# Stockwaage.net
KiCad netlist of a schematic drawn in EasyEDA
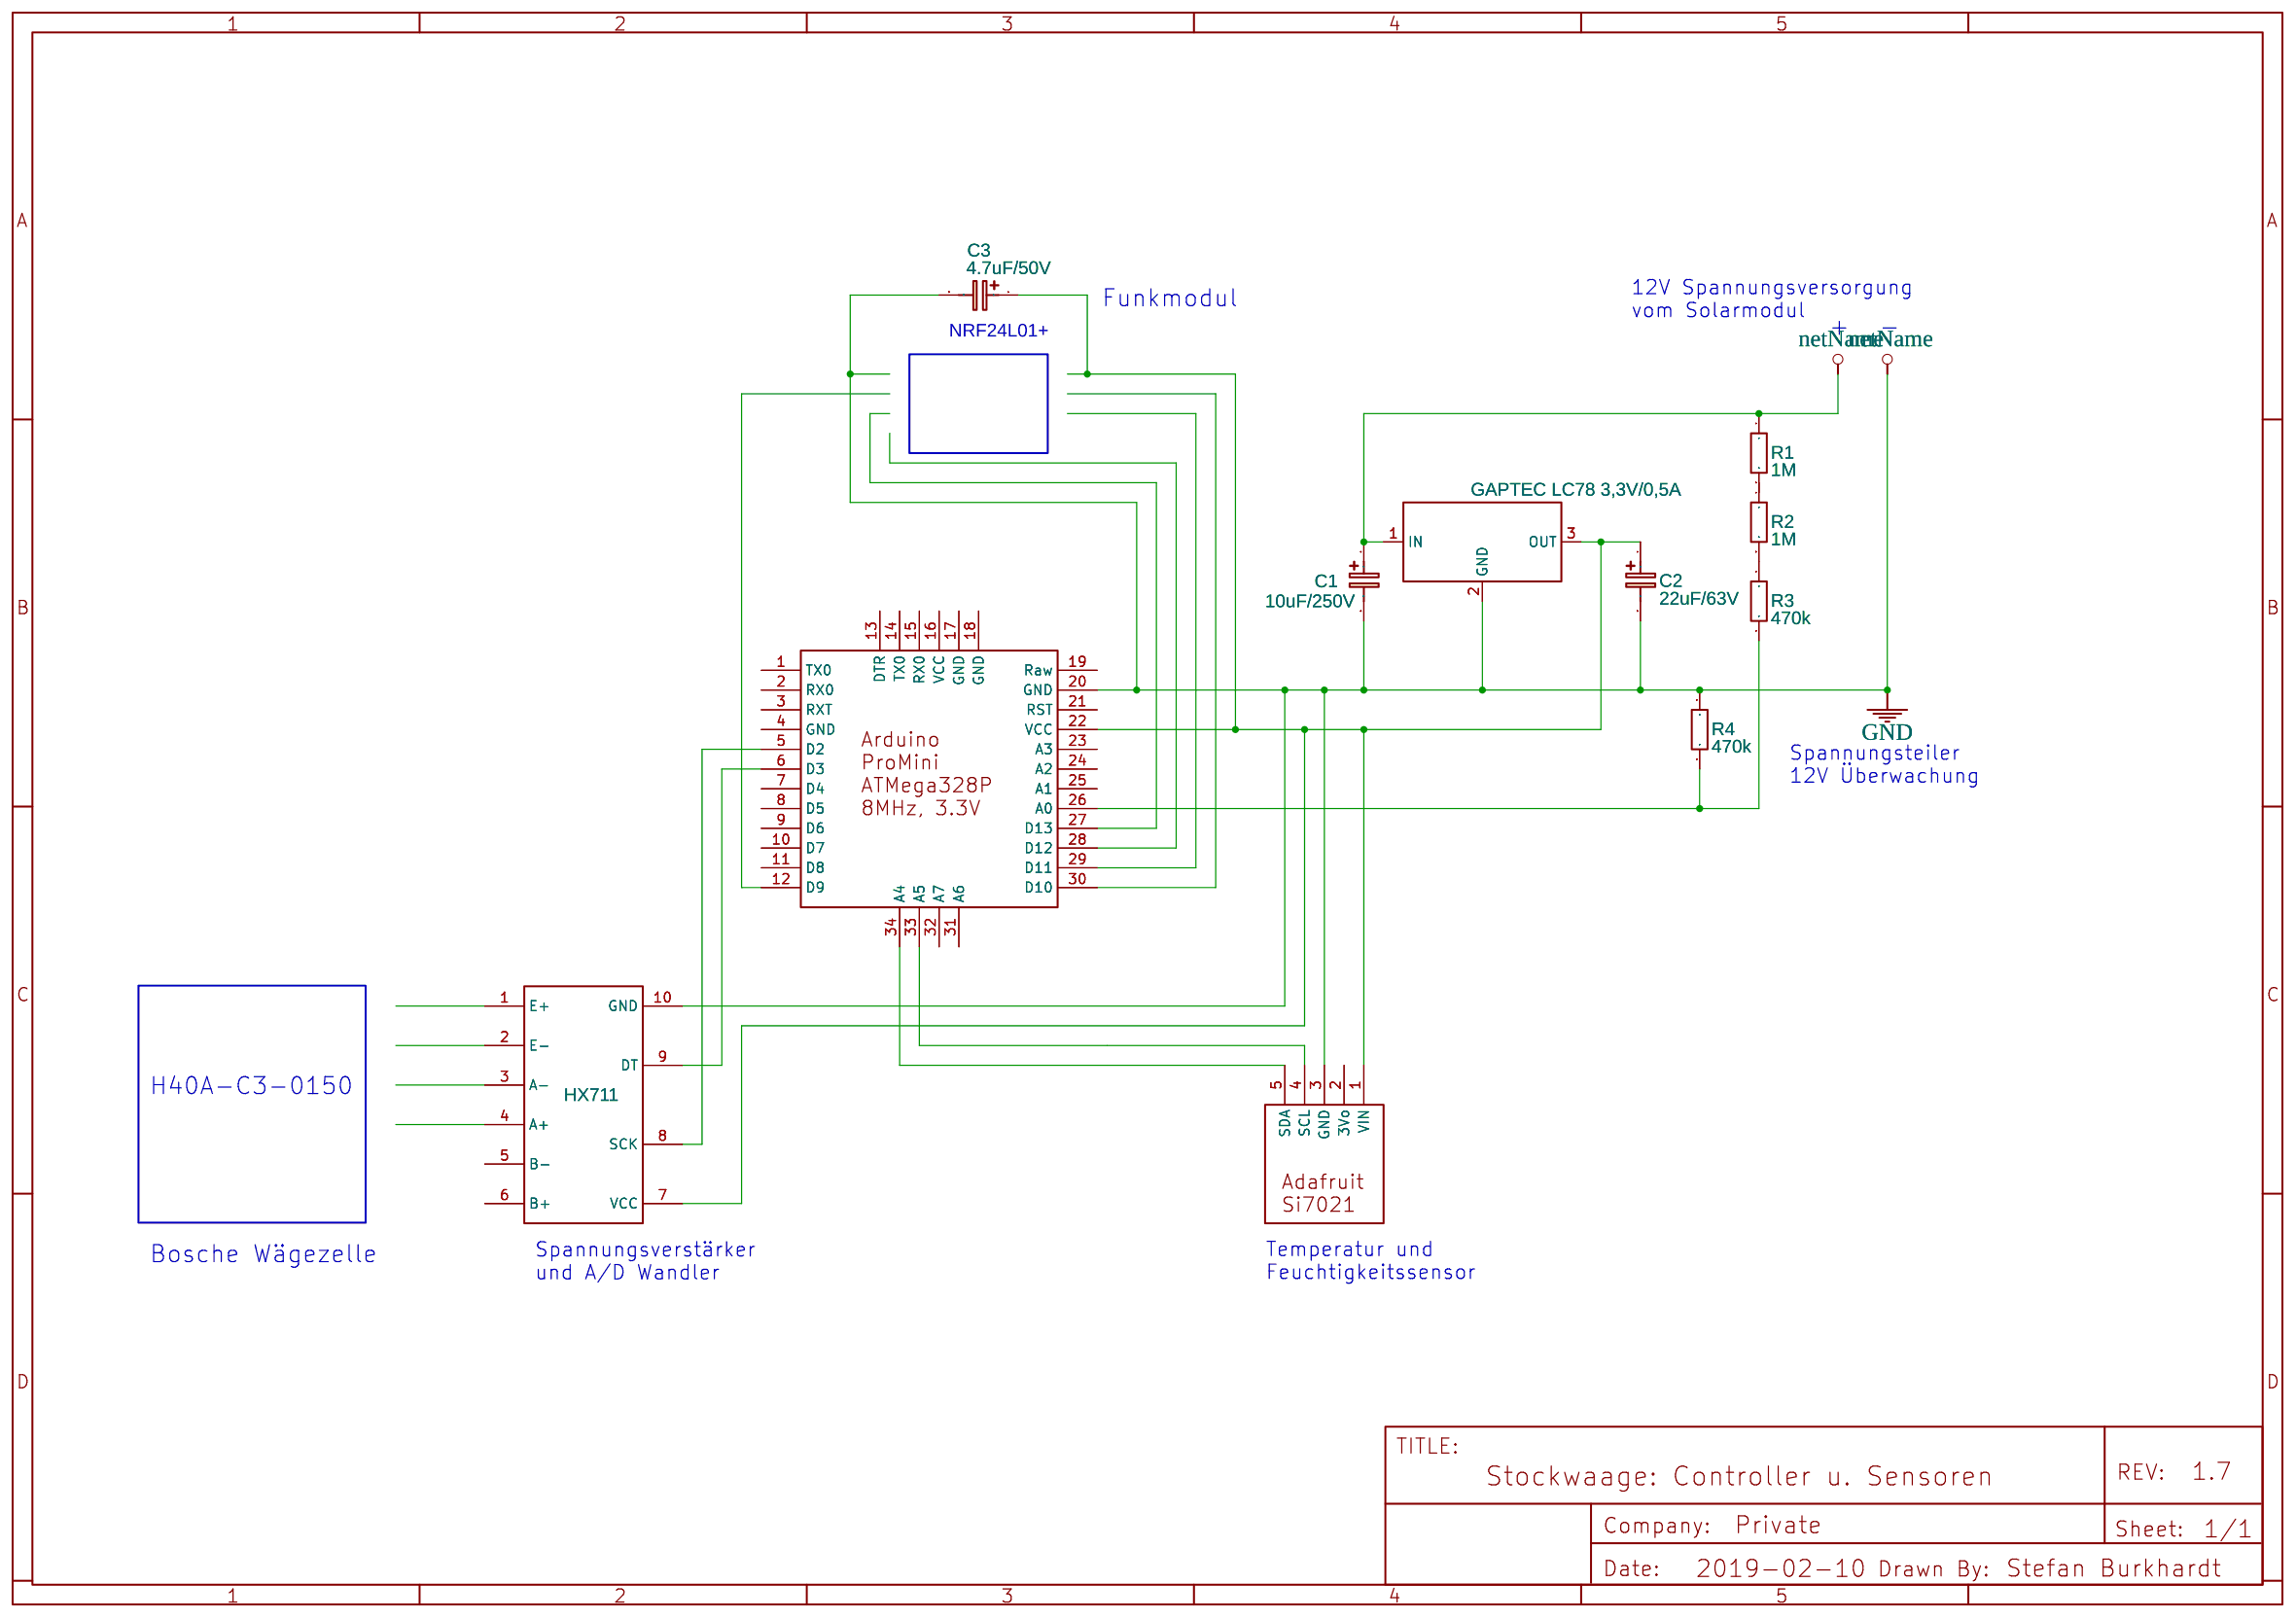
[diagram p0: schematic sheet]

(export (version "E")
  (design (tool "Eeschema 10.0.6"))
  (components
    (comp (ref "C1")
      (value "10uF/250V")
      (fields (field (name "BOM_Manufacturer Part") "?"))
      (libsource (lib "") (part "Cap_Electrolytic(TH)_D3.0XF1.5_EU"))
    )
    (comp (ref "C2")
      (value "22uF/63V")
      (fields (field (name "BOM_Manufacturer Part") "?"))
      (libsource (lib "") (part "Cap_Electrolytic(TH)_D3.0XF1.5_EU"))
    )
    (comp (ref "C3")
      (value "4.7uF/50V")
      (fields (field (name "BOM_Manufacturer Part") "?"))
      (libsource (lib "") (part "Cap_Electrolytic(TH)_D3.0XF1.5_EU_1"))
    )
    (comp (ref "R1")
      (value "1M")
      (fields (field (name "BOM_Manufacturer Part") "?"))
      (libsource (lib "") (part "Res_AXIAL-0.3(1/8W)_EU"))
    )
    (comp (ref "R2")
      (value "1M")
      (fields (field (name "BOM_Manufacturer Part") "?"))
      (libsource (lib "") (part "Res_AXIAL-0.3(1/8W)_EU"))
    )
    (comp (ref "R3")
      (value "470k")
      (fields (field (name "BOM_Manufacturer Part") "?"))
      (libsource (lib "") (part "Res_AXIAL-0.3(1/8W)_EU"))
    )
    (comp (ref "R4")
      (value "470k")
      (fields (field (name "BOM_Manufacturer Part") "?"))
      (libsource (lib "") (part "Res_AXIAL-0.3(1/8W)_EU"))
    )
    (comp (ref "U1")
      (value "Arduino ProMini ATMega328P 8MHz, 3.3V")
      (fields (field (name "BOM_Manufacturer Part") "Arduino ProMini3v3"))
      (libsource (lib "") (part "Unknown_580_380"))
    )
    (comp (ref "U2")
      (value "GAPTEC LC78 3,3V/0,5A")
      (fields (field (name "BOM_Manufacturer Part") "?"))
      (libsource (lib "") (part "Unknown_860_270"))
    )
    (comp (ref "U3")
      (value "Adafruit Si7021")
      (fields (field (name "BOM_Manufacturer Part") "?") (field (name "BOM_Supplier Part") "3251"))
      (libsource (lib "") (part "Unknown_810_555"))
    )
    (comp (ref "U5") (value "HX711") (libsource (lib "") (part "Unknown_405_545")))
  )
  (nets
    (net (code "1") (name "GND") (class "Default")
      (node (ref "C1") (pin "1") (pinfunction "1_1") (pintype "unspecified"))
      (node (ref "C1") (pin "2") (pinfunction "2_2") (pintype "unspecified"))
      (node (ref "C2") (pin "2") (pinfunction "2_2") (pintype "unspecified"))
      (node (ref "C3") (pin "2") (pinfunction "2_2") (pintype "unspecified"))
      (node (ref "R1") (pin "1") (pinfunction "1_1") (pintype "unspecified"))
      (node (ref "R4") (pin "1") (pinfunction "1_1") (pintype "unspecified"))
      (node (ref "U1") (pin "20") (pinfunction "GND_20") (pintype "unspecified"))
      (node (ref "U2") (pin "1") (pinfunction "IN_1") (pintype "unspecified"))
      (node (ref "U2") (pin "2") (pinfunction "GND_2") (pintype "unspecified"))
      (node (ref "U3") (pin "3") (pinfunction "GND_3") (pintype "unspecified"))
      (node (ref "U5") (pin "10") (pinfunction "GND_10") (pintype "unspecified"))
    )
    (net (code "2") (name "Net-(R2-Pad2)") (class "Default")
      (node (ref "R2") (pin "2") (pinfunction "2_2") (pintype "unspecified"))
      (node (ref "R3") (pin "1") (pinfunction "1_1") (pintype "unspecified"))
    )
    (net (code "3") (name "Net-(U1-A0)") (class "Default")
      (node (ref "R3") (pin "2") (pinfunction "2_2") (pintype "unspecified"))
      (node (ref "R4") (pin "2") (pinfunction "2_2") (pintype "unspecified"))
      (node (ref "U1") (pin "26") (pinfunction "A0_26") (pintype "unspecified"))
    )
    (net (code "4") (name "Net-(U1-A4)") (class "Default")
      (node (ref "U1") (pin "34") (pinfunction "A4_34") (pintype "unspecified"))
      (node (ref "U3") (pin "5") (pinfunction "SDA_5") (pintype "bidirectional"))
    )
    (net (code "5") (name "Net-(U1-A5)") (class "Default")
      (node (ref "U1") (pin "33") (pinfunction "A5_33") (pintype "unspecified"))
      (node (ref "U3") (pin "4") (pinfunction "SCL_4") (pintype "bidirectional"))
    )
    (net (code "6") (name "Net-(U1-D2)") (class "Default")
      (node (ref "U1") (pin "5") (pinfunction "D2_5") (pintype "unspecified"))
      (node (ref "U5") (pin "8") (pinfunction "SCK_8") (pintype "unspecified"))
    )
    (net (code "7") (name "Net-(U1-D3)") (class "Default")
      (node (ref "U1") (pin "6") (pinfunction "D3_6") (pintype "unspecified"))
      (node (ref "U5") (pin "9") (pinfunction "DT_9") (pintype "unspecified"))
    )
    (net (code "8") (name "Net-(U2-OUT)") (class "Default")
      (node (ref "C2") (pin "1") (pinfunction "1_1") (pintype "unspecified"))
      (node (ref "C3") (pin "1") (pinfunction "1_1") (pintype "unspecified"))
      (node (ref "U1") (pin "22") (pinfunction "VCC_22") (pintype "unspecified"))
      (node (ref "U2") (pin "3") (pinfunction "OUT_3") (pintype "unspecified"))
      (node (ref "U3") (pin "1") (pinfunction "VIN_1") (pintype "input"))
      (node (ref "U5") (pin "7") (pinfunction "VCC_7") (pintype "unspecified"))
    )
    (net (code "9") (name "unconnected-(R1-Pad2)") (class "Default")
      (node (ref "R1") (pin "2") (pinfunction "2_2") (pintype "unspecified"))
    )
    (net (code "10") (name "unconnected-(R2-Pad1)") (class "Default")
      (node (ref "R2") (pin "1") (pinfunction "1_1") (pintype "unspecified"))
    )
    (net (code "11") (name "unconnected-(U1-A1-Pad25)") (class "Default")
      (node (ref "U1") (pin "25") (pinfunction "A1_25") (pintype "unspecified"))
    )
    (net (code "12") (name "unconnected-(U1-A2-Pad24)") (class "Default")
      (node (ref "U1") (pin "24") (pinfunction "A2_24") (pintype "unspecified"))
    )
    (net (code "13") (name "unconnected-(U1-A3-Pad23)") (class "Default")
      (node (ref "U1") (pin "23") (pinfunction "A3_23") (pintype "unspecified"))
    )
    (net (code "14") (name "unconnected-(U1-A6-Pad31)") (class "Default")
      (node (ref "U1") (pin "31") (pinfunction "A6_31") (pintype "unspecified"))
    )
    (net (code "15") (name "unconnected-(U1-A7-Pad32)") (class "Default")
      (node (ref "U1") (pin "32") (pinfunction "A7_32") (pintype "unspecified"))
    )
    (net (code "16") (name "unconnected-(U1-D4-Pad7)") (class "Default")
      (node (ref "U1") (pin "7") (pinfunction "D4_7") (pintype "unspecified"))
    )
    (net (code "17") (name "unconnected-(U1-D5-Pad8)") (class "Default")
      (node (ref "U1") (pin "8") (pinfunction "D5_8") (pintype "unspecified"))
    )
    (net (code "18") (name "unconnected-(U1-D6-Pad9)") (class "Default")
      (node (ref "U1") (pin "9") (pinfunction "D6_9") (pintype "unspecified"))
    )
    (net (code "19") (name "unconnected-(U1-D7-Pad10)") (class "Default")
      (node (ref "U1") (pin "10") (pinfunction "D7_10") (pintype "unspecified"))
    )
    (net (code "20") (name "unconnected-(U1-D8-Pad11)") (class "Default")
      (node (ref "U1") (pin "11") (pinfunction "D8_11") (pintype "unspecified"))
    )
    (net (code "21") (name "unconnected-(U1-D9-Pad12)") (class "Default")
      (node (ref "U1") (pin "12") (pinfunction "D9_12") (pintype "unspecified"))
    )
    (net (code "22") (name "unconnected-(U1-D10-Pad30)") (class "Default")
      (node (ref "U1") (pin "30") (pinfunction "D10_30") (pintype "unspecified"))
    )
    (net (code "23") (name "unconnected-(U1-D11-Pad29)") (class "Default")
      (node (ref "U1") (pin "29") (pinfunction "D11_29") (pintype "unspecified"))
    )
    (net (code "24") (name "unconnected-(U1-D12-Pad28)") (class "Default")
      (node (ref "U1") (pin "28") (pinfunction "D12_28") (pintype "unspecified"))
    )
    (net (code "25") (name "unconnected-(U1-D13-Pad27)") (class "Default")
      (node (ref "U1") (pin "27") (pinfunction "D13_27") (pintype "unspecified"))
    )
    (net (code "26") (name "unconnected-(U1-DTR-Pad13)") (class "Default")
      (node (ref "U1") (pin "13") (pinfunction "DTR_13") (pintype "unspecified"))
    )
    (net (code "27") (name "unconnected-(U1-GND-Pad4)") (class "Default")
      (node (ref "U1") (pin "4") (pinfunction "GND_4") (pintype "unspecified"))
    )
    (net (code "28") (name "unconnected-(U1-GND-Pad17)") (class "Default")
      (node (ref "U1") (pin "17") (pinfunction "GND_17") (pintype "unspecified"))
    )
    (net (code "29") (name "unconnected-(U1-GND-Pad18)") (class "Default")
      (node (ref "U1") (pin "18") (pinfunction "GND_18") (pintype "unspecified"))
    )
    (net (code "30") (name "unconnected-(U1-RST-Pad21)") (class "Default")
      (node (ref "U1") (pin "21") (pinfunction "RST_21") (pintype "unspecified"))
    )
    (net (code "31") (name "unconnected-(U1-RX0-Pad2)") (class "Default")
      (node (ref "U1") (pin "2") (pinfunction "RX0_2") (pintype "unspecified"))
    )
    (net (code "32") (name "unconnected-(U1-RX0-Pad15)") (class "Default")
      (node (ref "U1") (pin "15") (pinfunction "RX0_15") (pintype "unspecified"))
    )
    (net (code "33") (name "unconnected-(U1-RXT-Pad3)") (class "Default")
      (node (ref "U1") (pin "3") (pinfunction "RXT_3") (pintype "unspecified"))
    )
    (net (code "34") (name "unconnected-(U1-Raw-Pad19)") (class "Default")
      (node (ref "U1") (pin "19") (pinfunction "Raw_19") (pintype "unspecified"))
    )
    (net (code "35") (name "unconnected-(U1-TX0-Pad1)") (class "Default")
      (node (ref "U1") (pin "1") (pinfunction "TX0_1") (pintype "unspecified"))
    )
    (net (code "36") (name "unconnected-(U1-TX0-Pad14)") (class "Default")
      (node (ref "U1") (pin "14") (pinfunction "TX0_14") (pintype "unspecified"))
    )
    (net (code "37") (name "unconnected-(U1-VCC-Pad16)") (class "Default")
      (node (ref "U1") (pin "16") (pinfunction "VCC_16") (pintype "unspecified"))
    )
    (net (code "38") (name "unconnected-(U3-3Vo-Pad2)") (class "Default")
      (node (ref "U3") (pin "2") (pinfunction "3Vo_2") (pintype "output"))
    )
    (net (code "39") (name "unconnected-(U5-A+-Pad4)") (class "Default")
      (node (ref "U5") (pin "4") (pinfunction "A+_4") (pintype "unspecified"))
    )
    (net (code "40") (name "unconnected-(U5-A--Pad3)") (class "Default")
      (node (ref "U5") (pin "3") (pinfunction "A-_3") (pintype "unspecified"))
    )
    (net (code "41") (name "unconnected-(U5-B+-Pad6)") (class "Default")
      (node (ref "U5") (pin "6") (pinfunction "B+_6") (pintype "unspecified"))
    )
    (net (code "42") (name "unconnected-(U5-B--Pad5)") (class "Default")
      (node (ref "U5") (pin "5") (pinfunction "B-_5") (pintype "unspecified"))
    )
    (net (code "43") (name "unconnected-(U5-E+-Pad1)") (class "Default")
      (node (ref "U5") (pin "1") (pinfunction "E+_1") (pintype "unspecified"))
    )
    (net (code "44") (name "unconnected-(U5-E--Pad2)") (class "Default")
      (node (ref "U5") (pin "2") (pinfunction "E-_2") (pintype "unspecified"))
    )
  )
)
